# LB-word-decoder.net
KiCad netlist of a schematic drawn in Altium Designer
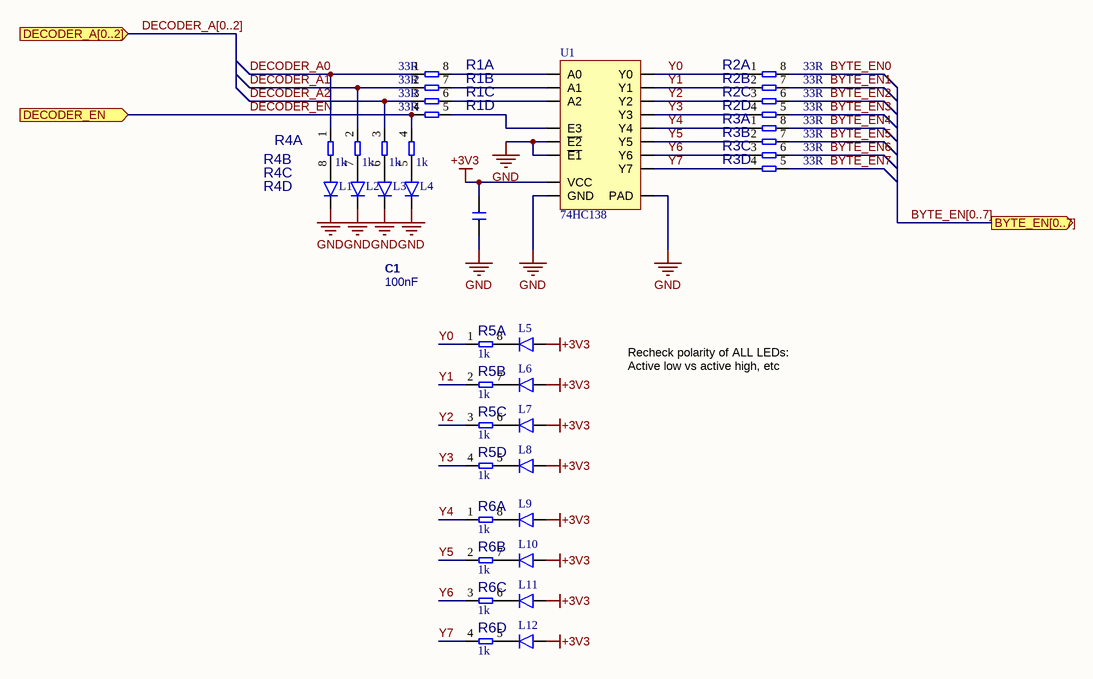
[diagram p0: LB-word-decoder.SchDoc]

(export (version "E")
  (design (tool "Eeschema 10.0.6"))
  (components
    (comp (ref "C1")
      (value "100nF")
      (footprint "C0603_N")
      (description "Capacitor MLCC")
      (fields
        (field (name "MANUFACTURER") "Yageo")
        (field (name "MANUFACTURER PART NUMBER") "CC0603KRX7R9BB104")
      )
      (libsource (lib "wes") (part "Capacitor"))
    )
    (comp (ref "L1") (value "LED") (footprint "LED 0603/1608") (libsource (lib "wes") (part "LED")))
    (comp (ref "L2") (value "LED") (footprint "LED 0603/1608") (libsource (lib "wes") (part "LED")))
    (comp (ref "L3") (value "LED") (footprint "LED 0603/1608") (libsource (lib "wes") (part "LED")))
    (comp (ref "L4") (value "LED") (footprint "LED 0603/1608") (libsource (lib "wes") (part "LED")))
    (comp (ref "L5") (value "LED") (footprint "LED 0603/1608") (libsource (lib "wes") (part "LED")))
    (comp (ref "L6") (value "LED") (footprint "LED 0603/1608") (libsource (lib "wes") (part "LED")))
    (comp (ref "L7") (value "LED") (footprint "LED 0603/1608") (libsource (lib "wes") (part "LED")))
    (comp (ref "L8") (value "LED") (footprint "LED 0603/1608") (libsource (lib "wes") (part "LED")))
    (comp (ref "L9") (value "LED") (footprint "LED 0603/1608") (libsource (lib "wes") (part "LED")))
    (comp (ref "L10") (value "LED") (footprint "LED 0603/1608") (libsource (lib "wes") (part "LED")))
    (comp (ref "L11") (value "LED") (footprint "LED 0603/1608") (libsource (lib "wes") (part "LED")))
    (comp (ref "L12") (value "LED") (footprint "LED 0603/1608") (libsource (lib "wes") (part "LED")))
    (comp (ref "R1")
      (value "33R")
      (footprint "YC164")
      (fields (field (name "Comment") "; 33R"))
      (libsource (lib "wes") (part "Resistor Array - 4P"))
    )
    (comp (ref "R2")
      (value "33R")
      (footprint "YC164")
      (fields (field (name "Comment") "; 33R"))
      (libsource (lib "wes") (part "Resistor Array - 4P"))
    )
    (comp (ref "R3")
      (value "33R")
      (footprint "YC164")
      (fields (field (name "Comment") "; 33R"))
      (libsource (lib "wes") (part "Resistor Array - 4P"))
    )
    (comp (ref "R4")
      (value "1k")
      (footprint "YC164")
      (fields (field (name "Comment") "; 1k"))
      (libsource (lib "wes") (part "Resistor Array - 4P"))
    )
    (comp (ref "R5")
      (value "1k")
      (footprint "YC164")
      (fields (field (name "Comment") "; 1k"))
      (libsource (lib "wes") (part "Resistor Array - 4P"))
    )
    (comp (ref "R6")
      (value "1k")
      (footprint "YC164")
      (fields (field (name "Comment") "; 1k"))
      (libsource (lib "wes") (part "Resistor Array - 4P"))
    )
    (comp (ref "U1")
      (value "74HC138")
      (footprint "DHVQFN16")
      (description "3 to 8 Decoder")
      (libsource (lib "wes") (part "74HC138"))
    )
  )
  (nets
    (net (code "1") (name "+3V3") (class "Default")
      (node (ref "C1") (pin "1") (pintype "passive"))
      (node (ref "L10") (pin "2") (pinfunction "A_2") (pintype "power_in"))
      (node (ref "L11") (pin "2") (pinfunction "A_2") (pintype "power_in"))
      (node (ref "L12") (pin "2") (pinfunction "A_2") (pintype "power_in"))
      (node (ref "L5") (pin "2") (pinfunction "A_2") (pintype "power_in"))
      (node (ref "L6") (pin "2") (pinfunction "A_2") (pintype "power_in"))
      (node (ref "L7") (pin "2") (pinfunction "A_2") (pintype "power_in"))
      (node (ref "L8") (pin "2") (pinfunction "A_2") (pintype "power_in"))
      (node (ref "L9") (pin "2") (pinfunction "A_2") (pintype "power_in"))
      (node (ref "U1") (pin "16") (pinfunction "VCC_16") (pintype "power_in"))
    )
    (net (code "2") (name "/BYTE_EN0") (class "Default")
      (node (ref "R2") (pin "8") (pinfunction "8_8") (pintype "passive"))
    )
    (net (code "3") (name "/BYTE_EN1") (class "Default")
      (node (ref "R2") (pin "7") (pinfunction "7_7") (pintype "passive"))
    )
    (net (code "4") (name "/BYTE_EN2") (class "Default")
      (node (ref "R2") (pin "6") (pinfunction "6_6") (pintype "passive"))
    )
    (net (code "5") (name "/BYTE_EN3") (class "Default")
      (node (ref "R2") (pin "5") (pinfunction "5_5") (pintype "passive"))
    )
    (net (code "6") (name "/BYTE_EN4") (class "Default")
      (node (ref "R3") (pin "8") (pinfunction "8_8") (pintype "passive"))
    )
    (net (code "7") (name "/BYTE_EN5") (class "Default")
      (node (ref "R3") (pin "7") (pinfunction "7_7") (pintype "passive"))
    )
    (net (code "8") (name "/BYTE_EN6") (class "Default")
      (node (ref "R3") (pin "6") (pinfunction "6_6") (pintype "passive"))
    )
    (net (code "9") (name "/BYTE_EN7") (class "Default")
      (node (ref "R3") (pin "5") (pinfunction "5_5") (pintype "passive"))
    )
    (net (code "11") (name "/DECODER_A0") (class "Default")
      (node (ref "R1") (pin "1") (pinfunction "1_1") (pintype "passive"))
      (node (ref "R4") (pin "1") (pinfunction "1_1") (pintype "passive"))
    )
    (net (code "12") (name "/DECODER_A1") (class "Default")
      (node (ref "R1") (pin "2") (pinfunction "2_2") (pintype "passive"))
      (node (ref "R4") (pin "2") (pinfunction "2_2") (pintype "passive"))
    )
    (net (code "13") (name "/DECODER_A2") (class "Default")
      (node (ref "R1") (pin "3") (pinfunction "3_3") (pintype "passive"))
      (node (ref "R4") (pin "3") (pinfunction "3_3") (pintype "passive"))
    )
    (net (code "15") (name "/DECODER_EN") (class "Default")
      (node (ref "R1") (pin "4") (pinfunction "4_4") (pintype "passive"))
      (node (ref "R4") (pin "4") (pinfunction "4_4") (pintype "passive"))
    )
    (net (code "16") (name "/Y0") (class "Default")
      (node (ref "R2") (pin "1") (pinfunction "1_1") (pintype "passive"))
      (node (ref "R5") (pin "1") (pinfunction "1_1") (pintype "passive"))
      (node (ref "U1") (pin "15") (pinfunction "Y0_15") (pintype "power_in"))
    )
    (net (code "17") (name "/Y1") (class "Default")
      (node (ref "R2") (pin "2") (pinfunction "2_2") (pintype "passive"))
      (node (ref "R5") (pin "2") (pinfunction "2_2") (pintype "passive"))
      (node (ref "U1") (pin "14") (pinfunction "Y1_14") (pintype "power_in"))
    )
    (net (code "18") (name "/Y2") (class "Default")
      (node (ref "R2") (pin "3") (pinfunction "3_3") (pintype "passive"))
      (node (ref "R5") (pin "3") (pinfunction "3_3") (pintype "passive"))
      (node (ref "U1") (pin "13") (pinfunction "Y2_13") (pintype "power_in"))
    )
    (net (code "19") (name "/Y3") (class "Default")
      (node (ref "R2") (pin "4") (pinfunction "4_4") (pintype "passive"))
      (node (ref "R5") (pin "4") (pinfunction "4_4") (pintype "passive"))
      (node (ref "U1") (pin "12") (pinfunction "Y3_12") (pintype "power_in"))
    )
    (net (code "20") (name "/Y4") (class "Default")
      (node (ref "R3") (pin "1") (pinfunction "1_1") (pintype "passive"))
      (node (ref "R6") (pin "1") (pinfunction "1_1") (pintype "passive"))
      (node (ref "U1") (pin "11") (pinfunction "Y4_11") (pintype "power_in"))
    )
    (net (code "21") (name "/Y5") (class "Default")
      (node (ref "R3") (pin "2") (pinfunction "2_2") (pintype "passive"))
      (node (ref "R6") (pin "2") (pinfunction "2_2") (pintype "passive"))
      (node (ref "U1") (pin "10") (pinfunction "Y5_10") (pintype "power_in"))
    )
    (net (code "22") (name "/Y6") (class "Default")
      (node (ref "R3") (pin "3") (pinfunction "3_3") (pintype "passive"))
      (node (ref "R6") (pin "3") (pinfunction "3_3") (pintype "passive"))
      (node (ref "U1") (pin "9") (pinfunction "Y6_9") (pintype "power_in"))
    )
    (net (code "23") (name "/Y7") (class "Default")
      (node (ref "R3") (pin "4") (pinfunction "4_4") (pintype "passive"))
      (node (ref "R6") (pin "4") (pinfunction "4_4") (pintype "passive"))
      (node (ref "U1") (pin "7") (pinfunction "Y7_7") (pintype "power_in"))
    )
    (net (code "24") (name "GND") (class "Default")
      (node (ref "C1") (pin "2") (pintype "passive"))
      (node (ref "L1") (pin "1") (pinfunction "K_1") (pintype "power_in"))
      (node (ref "L2") (pin "1") (pinfunction "K_1") (pintype "power_in"))
      (node (ref "L3") (pin "1") (pinfunction "K_1") (pintype "power_in"))
      (node (ref "L4") (pin "1") (pinfunction "K_1") (pintype "power_in"))
      (node (ref "U1") (pin "4") (pinfunction "~{E1}_4") (pintype "power_in"))
      (node (ref "U1") (pin "5") (pinfunction "~{E2}_5") (pintype "power_in"))
      (node (ref "U1") (pin "8") (pinfunction "GND_8") (pintype "power_in"))
      (node (ref "U1") (pin "PAD") (pinfunction "PAD_PAD") (pintype "power_in"))
    )
    (net (code "25") (name "Net-(L1-A)") (class "Default")
      (node (ref "L1") (pin "2") (pinfunction "A_2") (pintype "power_in"))
      (node (ref "R4") (pin "8") (pinfunction "8_8") (pintype "passive"))
    )
    (net (code "26") (name "Net-(L2-A)") (class "Default")
      (node (ref "L2") (pin "2") (pinfunction "A_2") (pintype "power_in"))
      (node (ref "R4") (pin "7") (pinfunction "7_7") (pintype "passive"))
    )
    (net (code "27") (name "Net-(L3-A)") (class "Default")
      (node (ref "L3") (pin "2") (pinfunction "A_2") (pintype "power_in"))
      (node (ref "R4") (pin "6") (pinfunction "6_6") (pintype "passive"))
    )
    (net (code "28") (name "Net-(L4-A)") (class "Default")
      (node (ref "L4") (pin "2") (pinfunction "A_2") (pintype "power_in"))
      (node (ref "R4") (pin "5") (pinfunction "5_5") (pintype "passive"))
    )
    (net (code "29") (name "Net-(L5-K)") (class "Default")
      (node (ref "L5") (pin "1") (pinfunction "K_1") (pintype "power_in"))
      (node (ref "R5") (pin "8") (pinfunction "8_8") (pintype "passive"))
    )
    (net (code "30") (name "Net-(L6-K)") (class "Default")
      (node (ref "L6") (pin "1") (pinfunction "K_1") (pintype "power_in"))
      (node (ref "R5") (pin "7") (pinfunction "7_7") (pintype "passive"))
    )
    (net (code "31") (name "Net-(L7-K)") (class "Default")
      (node (ref "L7") (pin "1") (pinfunction "K_1") (pintype "power_in"))
      (node (ref "R5") (pin "6") (pinfunction "6_6") (pintype "passive"))
    )
    (net (code "32") (name "Net-(L8-K)") (class "Default")
      (node (ref "L8") (pin "1") (pinfunction "K_1") (pintype "power_in"))
      (node (ref "R5") (pin "5") (pinfunction "5_5") (pintype "passive"))
    )
    (net (code "33") (name "Net-(L9-K)") (class "Default")
      (node (ref "L9") (pin "1") (pinfunction "K_1") (pintype "power_in"))
      (node (ref "R6") (pin "8") (pinfunction "8_8") (pintype "passive"))
    )
    (net (code "34") (name "Net-(L10-K)") (class "Default")
      (node (ref "L10") (pin "1") (pinfunction "K_1") (pintype "power_in"))
      (node (ref "R6") (pin "7") (pinfunction "7_7") (pintype "passive"))
    )
    (net (code "35") (name "Net-(L11-K)") (class "Default")
      (node (ref "L11") (pin "1") (pinfunction "K_1") (pintype "power_in"))
      (node (ref "R6") (pin "6") (pinfunction "6_6") (pintype "passive"))
    )
    (net (code "36") (name "Net-(L12-K)") (class "Default")
      (node (ref "L12") (pin "1") (pinfunction "K_1") (pintype "power_in"))
      (node (ref "R6") (pin "5") (pinfunction "5_5") (pintype "passive"))
    )
    (net (code "37") (name "Net-(U1-A0)") (class "Default")
      (node (ref "R1") (pin "8") (pinfunction "8_8") (pintype "passive"))
      (node (ref "U1") (pin "1") (pinfunction "A0_1") (pintype "power_in"))
    )
    (net (code "38") (name "Net-(U1-A1)") (class "Default")
      (node (ref "R1") (pin "7") (pinfunction "7_7") (pintype "passive"))
      (node (ref "U1") (pin "2") (pinfunction "A1_2") (pintype "power_in"))
    )
    (net (code "39") (name "Net-(U1-A2)") (class "Default")
      (node (ref "R1") (pin "6") (pinfunction "6_6") (pintype "passive"))
      (node (ref "U1") (pin "3") (pinfunction "A2_3") (pintype "power_in"))
    )
    (net (code "40") (name "Net-(U1-E3)") (class "Default")
      (node (ref "R1") (pin "5") (pinfunction "5_5") (pintype "passive"))
      (node (ref "U1") (pin "6") (pinfunction "E3_6") (pintype "power_in"))
    )
  )
)
